# REGULACION.net
KiCad netlist of a schematic drawn in Altium Designer
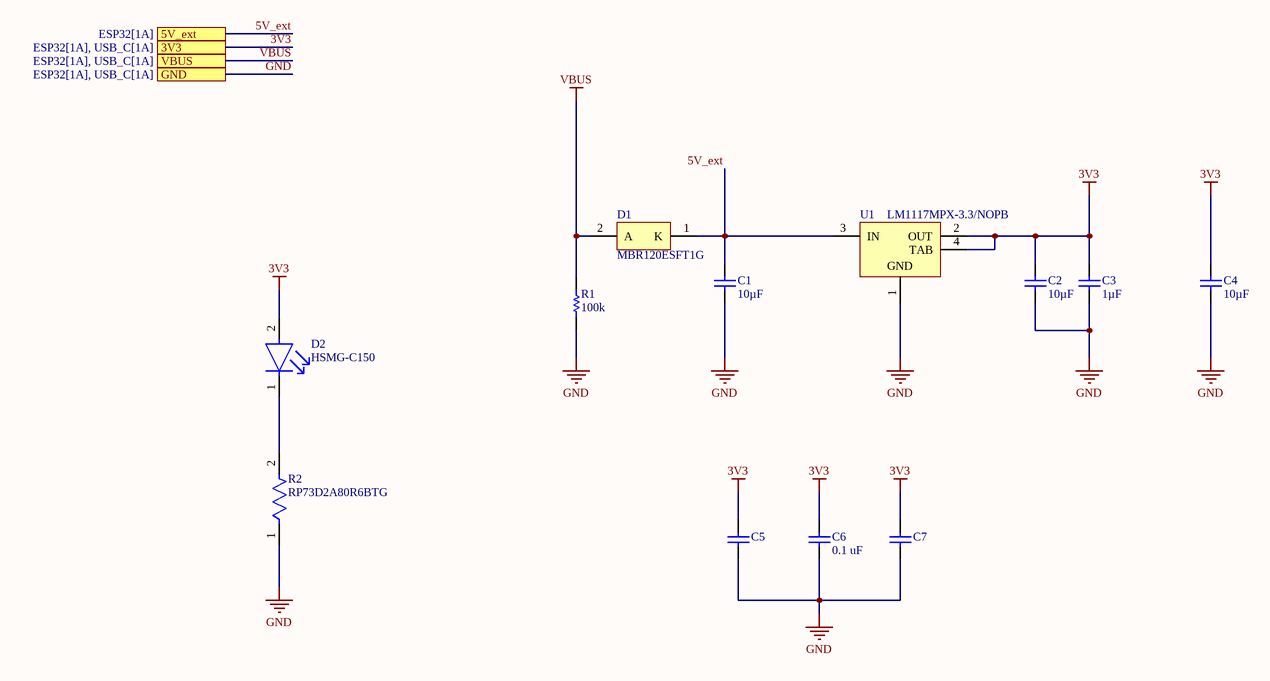
[diagram p0: REGULACION.SchDoc]

(export (version "E")
  (design (tool "Eeschema 10.0.6"))
  (components
    (comp (ref "C1")
      (value "10µF")
      (footprint "CAPC2013X140X50ML20T25")
      (description "10µF ±10% 16V Ceramic Capacitor X5R 0805 (2012 Metric)")
      (fields (field (name "PART NUMBER") "CL21A106KOQNNNG"))
      (libsource (lib "Altium Content Vault") (part "CAP"))
    )
    (comp (ref "C2")
      (value "10µF")
      (footprint "CAPC2013X140X50ML20T25")
      (description "10µF ±10% 16V Ceramic Capacitor X5R 0805 (2012 Metric)")
      (fields (field (name "PART NUMBER") "CL21A106KOQNNNG"))
      (libsource (lib "Altium Content Vault") (part "CAP"))
    )
    (comp (ref "C3")
      (value "1µF")
      (footprint "CAPC2013X145X50ML20T25")
      (description "1µF ±10% 16V Ceramic Capacitor X7R 0805 (2012 Metric)")
      (fields (field (name "MANUFACTURER") "Kemet") (field (name "PART NUMBER") "C0805C105K4RAC7800"))
      (libsource (lib "Altium Content Vault") (part "CAP"))
    )
    (comp (ref "C4")
      (value "10µF")
      (footprint "CAPC2013X140X50ML20T25")
      (description "10µF ±10% 16V Ceramic Capacitor X5R 0805 (2012 Metric)")
      (fields (field (name "PART NUMBER") "CL21A106KOQNNNG"))
      (libsource (lib "Altium Content Vault") (part "CAP"))
    )
    (comp (ref "C5")
      (value "C0805C106K4PACTU")
      (footprint "CAPC2013X140X50ML20T25")
      (description "10µF ±10% 16V Ceramic Capacitor X5R 0805 (2012 Metric)")
      (fields (field (name "PART NUMBER") "CL21A106KOQNNNG"))
      (libsource (lib "Altium Content Vault") (part "CAP"))
    )
    (comp (ref "C6")
      (value "0.1 uF")
      (footprint "CAPC2013X94X50ML20T25")
      (description "Chip Capacitor, Ceramic, 0.1 uF, 10%, 50 V, 0805, RoHS, Tape and Reel")
      (fields (field (name "MANUFACTURER") "AVX"))
      (libsource (lib "Altium Content Vault") (part "CAP-NP-2"))
    )
    (comp (ref "C7")
      (value "C0805C106K4PACTU")
      (footprint "CAPC2013X140X50ML20T25")
      (description "10µF ±10% 16V Ceramic Capacitor X5R 0805 (2012 Metric)")
      (fields (field (name "PART NUMBER") "CL21A106KOQNNNG"))
      (libsource (lib "Altium Content Vault") (part "CAP"))
    )
    (comp (ref "D1")
      (value "MBR120ESFT1G")
      (footprint "ONSC-SOD-123FL-2-498_V")
      (description "Schottky Power Rectifier, 2-Pin SOD-123, Pb-Free, Tape and Reel")
      (fields (field (name "MANUFACTURER") "On Semiconductor"))
      (libsource (lib "Altium Content Vault") (part "ONSC-D-K1A2-2_A"))
    )
    (comp (ref "D2")
      (value "HSMG-C150")
      (footprint "FP-HSMG-C150-MFG")
      (description "LED GREEN DIFFUSED 1206 SMD")
      (fields
        (field (name "MANUFACTURER") "Broadcom")
        (field (name "OCTOPART") "https://octopart.com/hsmg-c150-broadcom-71131304")
      )
      (libsource (lib "Altium Content Vault") (part "8706943c75ba83719d021d2fdc84c58"))
    )
    (comp (ref "R1")
      (value "100k")
      (footprint "RESC2013X60X40ML20T25")
      (description "100 kOhms ±0.1% 0.125W, 1/8W Chip Resistor 0805 (2012 Metric) Automotive AEC-Q200 Thin Film")
      (fields (field (name "PART NUMBER") "ERA6AEB104V") (field (name "MANUFACTURER") "Panasonic"))
      (libsource (lib "Altium Content Vault") (part "RES"))
    )
    (comp (ref "R2")
      (value "RP73D2A80R6BTG")
      (footprint "FP-RP732A-MFG")
      (description "RESISTOR, 0805 80.6Ω, 0.1% 15ppm/°C")
      (fields
        (field (name "OCTOPART") "https://octopart.com/rp73d2a80r6btg-te+connectivity-42011633")
        (field (name "MANUFACTURER") "TE Connectivity")
      )
      (libsource (lib "Altium Content Vault") (part "1029c3af85768c4190bb7ad29bc67b5"))
    )
    (comp (ref "U1")
      (value "LM1117MPX-3.3/NOPB")
      (footprint "DCY0004A_M")
      (description "800mA Low-Dropout Linear Regulator, 4-pin SOT-223, Pb-Free")
      (fields (field (name "MANUFACTURER") "Texas Instruments"))
      (libsource (lib "Altium Content Vault") (part "PM-REG-LM1086-SOT4"))
    )
  )
  (nets
    (net (code "1") (name "/5V_ext") (class "Default")
      (node (ref "C1") (pin "2") (pinfunction "2_2") (pintype "passive"))
      (node (ref "D1") (pin "1") (pinfunction "K_1") (pintype "passive"))
      (node (ref "U1") (pin "3") (pinfunction "IN_3") (pintype "power_in"))
    )
    (net (code "2") (name "3V3") (class "Default")
      (node (ref "C2") (pin "2") (pinfunction "2_2") (pintype "passive"))
      (node (ref "C3") (pin "2") (pinfunction "2_2") (pintype "passive"))
      (node (ref "C4") (pin "2") (pinfunction "2_2") (pintype "passive"))
      (node (ref "C5") (pin "2") (pinfunction "2_2") (pintype "passive"))
      (node (ref "C6") (pin "2") (pinfunction "2_2") (pintype "passive"))
      (node (ref "C7") (pin "2") (pinfunction "2_2") (pintype "passive"))
      (node (ref "D2") (pin "2") (pinfunction "A_2") (pintype "passive"))
      (node (ref "U1") (pin "2") (pinfunction "OUT_2") (pintype "power_in"))
      (node (ref "U1") (pin "4") (pinfunction "TAB_4") (pintype "power_in"))
    )
    (net (code "3") (name "GND") (class "Default")
      (node (ref "C1") (pin "1") (pinfunction "1_1") (pintype "passive"))
      (node (ref "C2") (pin "1") (pinfunction "1_1") (pintype "passive"))
      (node (ref "C3") (pin "1") (pinfunction "1_1") (pintype "passive"))
      (node (ref "C4") (pin "1") (pinfunction "1_1") (pintype "passive"))
      (node (ref "C5") (pin "1") (pinfunction "1_1") (pintype "passive"))
      (node (ref "C6") (pin "1") (pinfunction "1_1") (pintype "passive"))
      (node (ref "C7") (pin "1") (pinfunction "1_1") (pintype "passive"))
      (node (ref "R1") (pin "1") (pinfunction "1_1") (pintype "passive"))
      (node (ref "R2") (pin "1") (pinfunction "1_1") (pintype "passive"))
      (node (ref "U1") (pin "1") (pinfunction "GND_1") (pintype "power_in"))
    )
    (net (code "4") (name "Net-(D2-C)") (class "Default")
      (node (ref "D2") (pin "1") (pinfunction "C_1") (pintype "passive"))
      (node (ref "R2") (pin "2") (pinfunction "2_2") (pintype "passive"))
    )
    (net (code "5") (name "VBUS") (class "Default")
      (node (ref "D1") (pin "2") (pinfunction "A_2") (pintype "passive"))
      (node (ref "R1") (pin "2") (pinfunction "2_2") (pintype "passive"))
    )
  )
)
